# XIAO_S3.net
KiCad netlist of a schematic drawn in Altium Designer
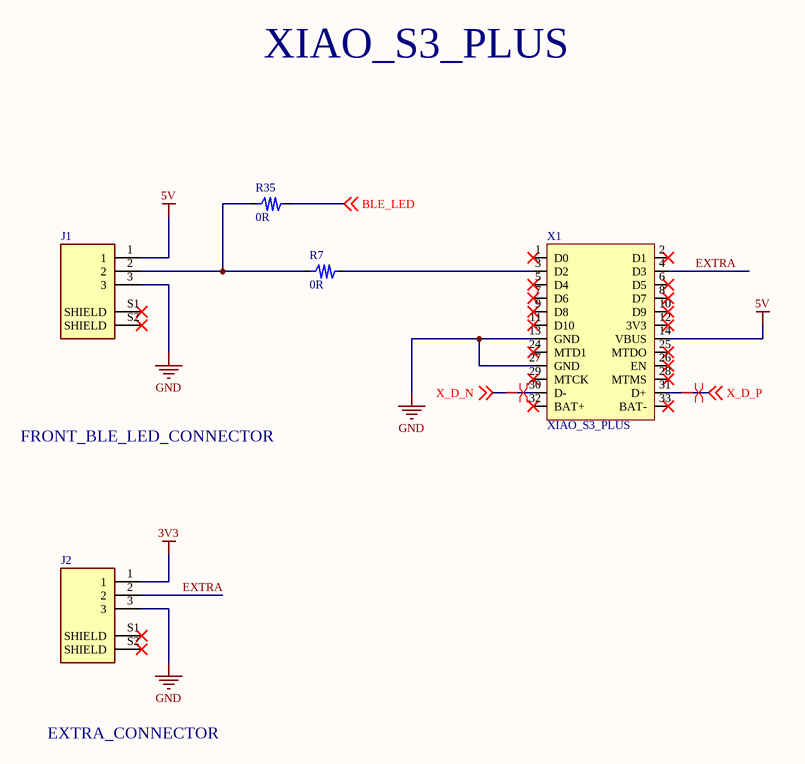
[diagram p0: XIAO_S3.SchDoc]

(export (version "E")
  (design (tool "Eeschema 10.0.6"))
  (components
    (comp (ref "J1")
      (value "SM03B-SRSS-TB(LF)(SN)")
      (footprint "JST_SM03B-SRSS-TB(LF)(SN)")
      (description "Connector Header Surface Mount, Right Angle 3 position 0.039 (1.00mm)")
      (libsource (lib "Schlib2") (part "SM03B-SRSS-TB(LF)(SN)"))
    )
    (comp (ref "J2")
      (value "SM03B-SRSS-TB(LF)(SN)")
      (footprint "JST_SM03B-SRSS-TB(LF)(SN)")
      (description "Connector Header Surface Mount, Right Angle 3 position 0.039 (1.00mm)")
      (libsource (lib "Schlib2") (part "SM03B-SRSS-TB(LF)(SN)"))
    )
    (comp (ref "R7")
      (value "0R")
      (footprint "RES 0603")
      (fields (field (name "PART NUMBER") "RC0603JR-070RL"))
      (libsource (lib "Schlib2") (part "Resistor"))
    )
    (comp (ref "R35")
      (value "0R")
      (footprint "RES 0603")
      (fields (field (name "PART NUMBER") "RC0603JR-070RL"))
      (libsource (lib "Schlib2") (part "Resistor"))
    )
    (comp (ref "X1")
      (value "XIAO_S3_PLUS")
      (footprint "XIAO_S3_PLUS")
      (libsource (lib "Schlib2") (part "XIAO_S3_PLUS"))
    )
  )
  (nets
    (net (code "1") (name "/EXTRA") (class "Default")
      (node (ref "J2") (pin "2") (pinfunction "2_2") (pintype "passive"))
      (node (ref "X1") (pin "4") (pinfunction "D3_4") (pintype "passive"))
    )
    (net (code "2") (name "3V3") (class "Default")
      (node (ref "J2") (pin "1") (pinfunction "1_1") (pintype "passive"))
    )
    (net (code "3") (name "5V") (class "Default")
      (node (ref "J1") (pin "1") (pinfunction "1_1") (pintype "passive"))
      (node (ref "X1") (pin "14") (pinfunction "VBUS_14") (pintype "passive"))
    )
    (net (code "4") (name "BLE_LED") (class "Default")
      (node (ref "R35") (pin "2") (pinfunction "2_2") (pintype "passive"))
    )
    (net (code "5") (name "GND") (class "Default")
      (node (ref "J1") (pin "3") (pinfunction "3_3") (pintype "passive"))
      (node (ref "J2") (pin "3") (pinfunction "3_3") (pintype "passive"))
      (node (ref "X1") (pin "13") (pinfunction "GND_13") (pintype "passive"))
      (node (ref "X1") (pin "27") (pinfunction "GND_27") (pintype "passive"))
    )
    (net (code "6") (name "Net-(J1-Pad2)") (class "Default")
      (node (ref "J1") (pin "2") (pinfunction "2_2") (pintype "passive"))
      (node (ref "R35") (pin "1") (pinfunction "1_1") (pintype "passive"))
      (node (ref "R7") (pin "1") (pinfunction "1_1") (pintype "passive"))
    )
    (net (code "7") (name "Net-(X1-D2)") (class "Default")
      (node (ref "R7") (pin "2") (pinfunction "2_2") (pintype "passive"))
      (node (ref "X1") (pin "3") (pinfunction "D2_3") (pintype "passive"))
    )
    (net (code "8") (name "X_D_N") (class "Default")
      (node (ref "X1") (pin "30") (pinfunction "D-_30") (pintype "passive"))
    )
    (net (code "9") (name "X_D_P") (class "Default")
      (node (ref "X1") (pin "31") (pinfunction "D+_31") (pintype "passive"))
    )
    (net (code "10") (name "unconnected-(J1-SHIELD-PadS1)") (class "Default")
      (node (ref "J1") (pin "S1") (pinfunction "SHIELD_S1") (pintype "passive+no_connect"))
    )
    (net (code "11") (name "unconnected-(J1-SHIELD-PadS2)") (class "Default")
      (node (ref "J1") (pin "S2") (pinfunction "SHIELD_S2") (pintype "passive+no_connect"))
    )
    (net (code "12") (name "unconnected-(J2-SHIELD-PadS1)") (class "Default")
      (node (ref "J2") (pin "S1") (pinfunction "SHIELD_S1") (pintype "passive+no_connect"))
    )
    (net (code "13") (name "unconnected-(J2-SHIELD-PadS2)") (class "Default")
      (node (ref "J2") (pin "S2") (pinfunction "SHIELD_S2") (pintype "passive+no_connect"))
    )
    (net (code "14") (name "unconnected-(X1-3V3-Pad12)") (class "Default")
      (node (ref "X1") (pin "12") (pinfunction "3V3_12") (pintype "passive+no_connect"))
    )
    (net (code "15") (name "unconnected-(X1-BAT+-Pad32)") (class "Default")
      (node (ref "X1") (pin "32") (pinfunction "BAT+_32") (pintype "passive+no_connect"))
    )
    (net (code "16") (name "unconnected-(X1-BAT--Pad33)") (class "Default")
      (node (ref "X1") (pin "33") (pinfunction "BAT-_33") (pintype "passive+no_connect"))
    )
    (net (code "17") (name "unconnected-(X1-D0-Pad1)") (class "Default")
      (node (ref "X1") (pin "1") (pinfunction "D0_1") (pintype "passive+no_connect"))
    )
    (net (code "18") (name "unconnected-(X1-D1-Pad2)") (class "Default")
      (node (ref "X1") (pin "2") (pinfunction "D1_2") (pintype "passive+no_connect"))
    )
    (net (code "19") (name "unconnected-(X1-D4-Pad5)") (class "Default")
      (node (ref "X1") (pin "5") (pinfunction "D4_5") (pintype "passive+no_connect"))
    )
    (net (code "20") (name "unconnected-(X1-D5-Pad6)") (class "Default")
      (node (ref "X1") (pin "6") (pinfunction "D5_6") (pintype "passive+no_connect"))
    )
    (net (code "21") (name "unconnected-(X1-D6-Pad7)") (class "Default")
      (node (ref "X1") (pin "7") (pinfunction "D6_7") (pintype "passive+no_connect"))
    )
    (net (code "22") (name "unconnected-(X1-D7-Pad8)") (class "Default")
      (node (ref "X1") (pin "8") (pinfunction "D7_8") (pintype "passive+no_connect"))
    )
    (net (code "23") (name "unconnected-(X1-D8-Pad9)") (class "Default")
      (node (ref "X1") (pin "9") (pinfunction "D8_9") (pintype "passive+no_connect"))
    )
    (net (code "24") (name "unconnected-(X1-D9-Pad10)") (class "Default")
      (node (ref "X1") (pin "10") (pinfunction "D9_10") (pintype "passive+no_connect"))
    )
    (net (code "25") (name "unconnected-(X1-D10-Pad11)") (class "Default")
      (node (ref "X1") (pin "11") (pinfunction "D10_11") (pintype "passive+no_connect"))
    )
    (net (code "26") (name "unconnected-(X1-EN-Pad26)") (class "Default")
      (node (ref "X1") (pin "26") (pinfunction "EN_26") (pintype "passive+no_connect"))
    )
    (net (code "27") (name "unconnected-(X1-MTCK-Pad29)") (class "Default")
      (node (ref "X1") (pin "29") (pinfunction "MTCK_29") (pintype "passive+no_connect"))
    )
    (net (code "28") (name "unconnected-(X1-MTD1-Pad24)") (class "Default")
      (node (ref "X1") (pin "24") (pinfunction "MTD1_24") (pintype "passive+no_connect"))
    )
    (net (code "29") (name "unconnected-(X1-MTDO-Pad25)") (class "Default")
      (node (ref "X1") (pin "25") (pinfunction "MTDO_25") (pintype "passive+no_connect"))
    )
    (net (code "30") (name "unconnected-(X1-MTMS-Pad28)") (class "Default")
      (node (ref "X1") (pin "28") (pinfunction "MTMS_28") (pintype "passive+no_connect"))
    )
  )
)
